# Motor_driver.net
KiCad netlist of a schematic drawn in Altium Designer
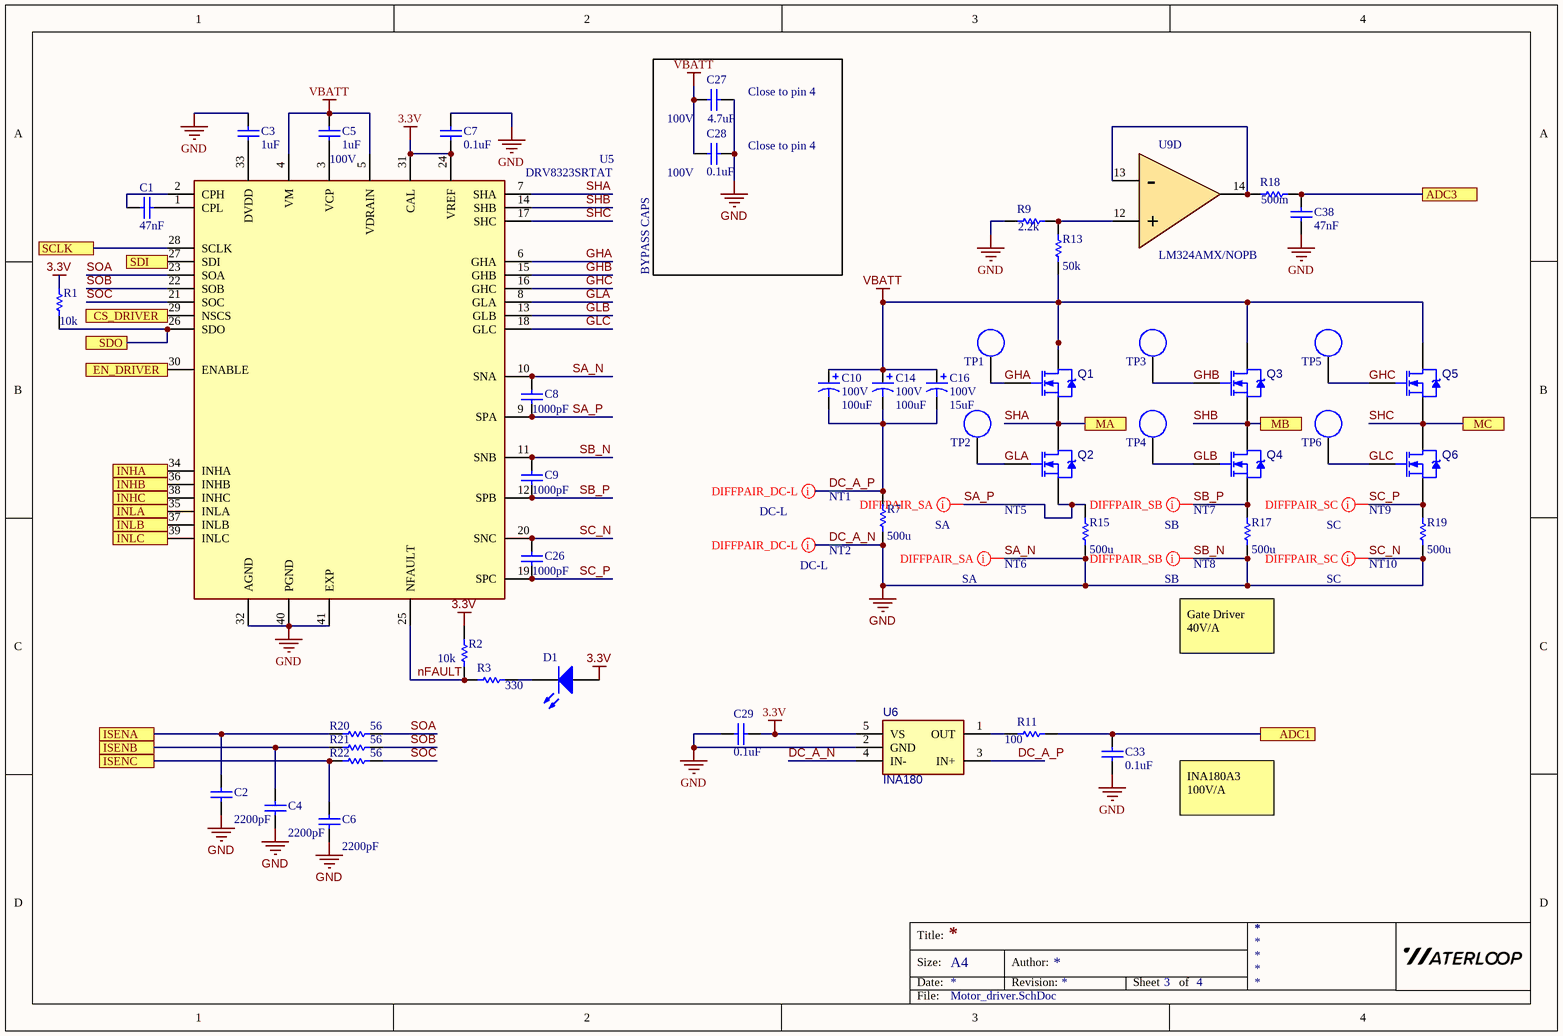
[diagram p0: Motor_driver.SchDoc]

(export (version "E")
  (design (tool "Eeschema 10.0.6"))
  (components
    (comp (ref "C1")
      (value "47nF")
      (footprint "0805 - Capacitor")
      (description "CL21B104KCFNNNE, MULTILAYER CERAMIC CAPACITORS MLCC - SMD/SMT 100NF 100V 0805 ROHS")
      (fields (field (name "Comment") "100V"))
      (libsource (lib "General") (part "Capacitor - Nonpolarized"))
    )
    (comp (ref "C2")
      (value "2200pF")
      (footprint "0805 - Capacitor")
      (description "TDK C2012X7S2A105KT000N, 1UF ±10% 100V X7S 0805 MULTILAYER CERAMIC CAPACITORS MLCC - SMD/SMT ROHS")
      (fields (field (name "Comment") "10V"))
      (libsource (lib "General") (part "Capacitor - Nonpolarized"))
    )
    (comp (ref "C3")
      (value "1uF")
      (footprint "0805 - Capacitor")
      (description "TDK C2012X7S2A105KT000N, 1UF ±10% 100V X7S 0805 MULTILAYER CERAMIC CAPACITORS MLCC - SMD/SMT ROHS")
      (fields (field (name "Comment") "100V"))
      (libsource (lib "General") (part "Capacitor - Nonpolarized"))
    )
    (comp (ref "C4")
      (value "2200pF")
      (footprint "0805 - Capacitor")
      (description "TDK C2012X7S2A105KT000N, 1UF ±10% 100V X7S 0805 MULTILAYER CERAMIC CAPACITORS MLCC - SMD/SMT ROHS")
      (fields (field (name "Comment") "10V"))
      (libsource (lib "General") (part "Capacitor - Nonpolarized"))
    )
    (comp (ref "C5")
      (value "100V")
      (footprint "0805 - Capacitor")
      (description "TDK C2012X7S2A105KT000N, 1UF ±10% 100V X7S 0805 MULTILAYER CERAMIC CAPACITORS MLCC - SMD/SMT ROHS")
      (fields (field (name "ALTIUM_VALUE") "1uF"))
      (libsource (lib "General") (part "Capacitor - Nonpolarized"))
    )
    (comp (ref "C6")
      (value "2200pF")
      (footprint "0805 - Capacitor")
      (description "TDK C2012X7S2A105KT000N, 1UF ±10% 100V X7S 0805 MULTILAYER CERAMIC CAPACITORS MLCC - SMD/SMT ROHS")
      (fields (field (name "Comment") "10V"))
      (libsource (lib "General") (part "Capacitor - Nonpolarized"))
    )
    (comp (ref "C7")
      (value "0.1uF")
      (footprint "0805 - Capacitor")
      (description "CL21B104KCFNNNE, MULTILAYER CERAMIC CAPACITORS MLCC - SMD/SMT 100NF 100V 0805 ROHS")
      (fields (field (name "Comment") "100V"))
      (libsource (lib "General") (part "Capacitor - Nonpolarized"))
    )
    (comp (ref "C8")
      (value "1000pF")
      (footprint "0805 - Capacitor")
      (description "TDK C2012X7S2A105KT000N, 1UF ±10% 100V X7S 0805 MULTILAYER CERAMIC CAPACITORS MLCC - SMD/SMT ROHS")
      (fields (field (name "Comment") "10V"))
      (libsource (lib "General") (part "Capacitor - Nonpolarized"))
    )
    (comp (ref "C9")
      (value "1000pF")
      (footprint "0805 - Capacitor")
      (description "TDK C2012X7S2A105KT000N, 1UF ±10% 100V X7S 0805 MULTILAYER CERAMIC CAPACITORS MLCC - SMD/SMT ROHS")
      (fields (field (name "Comment") "10V"))
      (libsource (lib "General") (part "Capacitor - Nonpolarized"))
    )
    (comp (ref "C10")
      (value "100V")
      (footprint "Electrolytic Cap")
      (fields (field (name "ALTIUM_VALUE") "100uF") (field (name "PUBLISHER") "Altium Limited"))
      (libsource (lib "Miscellaneous Devices") (part "Cap Pol3"))
    )
    (comp (ref "C14")
      (value "100V")
      (footprint "Electrolytic Cap")
      (fields (field (name "ALTIUM_VALUE") "100uF") (field (name "PUBLISHER") "Altium Limited"))
      (libsource (lib "Miscellaneous Devices") (part "Cap Pol3"))
    )
    (comp (ref "C16")
      (value "100V")
      (footprint "Electrolytic Cap")
      (fields (field (name "ALTIUM_VALUE") "15uF") (field (name "PUBLISHER") "Altium Limited"))
      (libsource (lib "Miscellaneous Devices") (part "Cap Pol3"))
    )
    (comp (ref "C26")
      (value "1000pF")
      (footprint "0805 - Capacitor")
      (description "TDK C2012X7S2A105KT000N, 1UF ±10% 100V X7S 0805 MULTILAYER CERAMIC CAPACITORS MLCC - SMD/SMT ROHS")
      (fields (field (name "Comment") "10V"))
      (libsource (lib "General") (part "Capacitor - Nonpolarized"))
    )
    (comp (ref "C27")
      (value "100V")
      (footprint "1210 - Capacitor")
      (description "TDK C2012X7S2A105KT000N, 1UF ±10% 100V X7S 0805 MULTILAYER CERAMIC CAPACITORS MLCC - SMD/SMT ROHS")
      (fields (field (name "ALTIUM_VALUE") "4.7uF"))
      (libsource (lib "General") (part "Capacitor - Nonpolarized"))
    )
    (comp (ref "C28")
      (value "100V")
      (footprint "0805 - Capacitor")
      (description "CL21B104KCFNNNE, MULTILAYER CERAMIC CAPACITORS MLCC - SMD/SMT 100NF 100V 0805 ROHS")
      (fields (field (name "ALTIUM_VALUE") "0.1uF"))
      (libsource (lib "General") (part "Capacitor - Nonpolarized"))
    )
    (comp (ref "C29")
      (value "0.1uF")
      (footprint "0805 - Capacitor")
      (description "CL21B104KCFNNNE, MULTILAYER CERAMIC CAPACITORS MLCC - SMD/SMT 100NF 100V 0805 ROHS")
      (fields (field (name "Comment") "100V"))
      (libsource (lib "General") (part "Capacitor - Nonpolarized"))
    )
    (comp (ref "C33")
      (value "0.1uF")
      (footprint "0805 - Capacitor")
      (description "CL21B104KCFNNNE, MULTILAYER CERAMIC CAPACITORS MLCC - SMD/SMT 100NF 100V 0805 ROHS")
      (fields (field (name "Comment") "100V"))
      (libsource (lib "General") (part "Capacitor - Nonpolarized"))
    )
    (comp (ref "C38")
      (value "47nF")
      (footprint "0805 - Capacitor")
      (description "CL21B104KCFNNNE, MULTILAYER CERAMIC CAPACITORS MLCC - SMD/SMT 100NF 100V 0805 ROHS")
      (fields (field (name "Comment") "100V"))
      (libsource (lib "General") (part "Capacitor - Nonpolarized"))
    )
    (comp (ref "D1")
      (value "150080SS75000")
      (footprint "0805_A")
      (description "SMD mono-color Chip LED, WL-SMCW, Super Red")
      (fields (field (name "MANUFACTURER") "Wuerth Elektronik"))
      (libsource (lib "Altium Content Vault") (part "WE-LED_K1A2-2"))
    )
    (comp (ref "NT1") (value "NetTie") (footprint "Net Tie") (libsource (lib "General") (part "Net Tie")))
    (comp (ref "NT2") (value "NetTie") (footprint "Net Tie") (libsource (lib "General") (part "Net Tie")))
    (comp (ref "NT5") (value "NetTie") (footprint "Net Tie") (libsource (lib "General") (part "Net Tie")))
    (comp (ref "NT6") (value "NetTie") (footprint "Net Tie") (libsource (lib "General") (part "Net Tie")))
    (comp (ref "NT7") (value "NetTie") (footprint "Net Tie") (libsource (lib "General") (part "Net Tie")))
    (comp (ref "NT8") (value "NetTie") (footprint "Net Tie") (libsource (lib "General") (part "Net Tie")))
    (comp (ref "NT9") (value "NetTie") (footprint "Net Tie") (libsource (lib "General") (part "Net Tie")))
    (comp (ref "NT10") (value "NetTie") (footprint "Net Tie") (libsource (lib "General") (part "Net Tie")))
    (comp (ref "Q1")
      (value "NMOS-2")
      (footprint "TO254P1651X1067X470-3")
      (description "N-Channel Power MOSFET")
      (fields (field (name "PUBLISHER") "Altium Limited"))
      (libsource (lib "Miscellaneous Devices") (part "NMOS-2"))
    )
    (comp (ref "Q2")
      (value "NMOS-2")
      (footprint "TO254P1651X1067X470-3")
      (description "N-Channel Power MOSFET")
      (fields (field (name "PUBLISHER") "Altium Limited"))
      (libsource (lib "Miscellaneous Devices") (part "NMOS-2"))
    )
    (comp (ref "Q3")
      (value "NMOS-2")
      (footprint "TO254P1651X1067X470-3")
      (description "N-Channel Power MOSFET")
      (fields (field (name "PUBLISHER") "Altium Limited"))
      (libsource (lib "Miscellaneous Devices") (part "NMOS-2"))
    )
    (comp (ref "Q4")
      (value "NMOS-2")
      (footprint "TO254P1651X1067X470-3")
      (description "N-Channel Power MOSFET")
      (fields (field (name "PUBLISHER") "Altium Limited"))
      (libsource (lib "Miscellaneous Devices") (part "NMOS-2"))
    )
    (comp (ref "Q5")
      (value "NMOS-2")
      (footprint "TO254P1651X1067X470-3")
      (description "N-Channel Power MOSFET")
      (fields (field (name "PUBLISHER") "Altium Limited"))
      (libsource (lib "Miscellaneous Devices") (part "NMOS-2"))
    )
    (comp (ref "Q6")
      (value "NMOS-2")
      (footprint "TO254P1651X1067X470-3")
      (description "N-Channel Power MOSFET")
      (fields (field (name "PUBLISHER") "Altium Limited"))
      (libsource (lib "Miscellaneous Devices") (part "NMOS-2"))
    )
    (comp (ref "R1")
      (value "10k")
      (footprint "0603 - Resistor")
      (description "Resistor")
      (libsource (lib "General") (part "Resistor"))
    )
    (comp (ref "R2")
      (value "10k")
      (footprint "0603 - Resistor")
      (description "Resistor")
      (libsource (lib "General") (part "Resistor"))
    )
    (comp (ref "R3")
      (value "330")
      (footprint "0603 - Resistor")
      (description "Resistor")
      (libsource (lib "General") (part "Resistor"))
    )
    (comp (ref "R7")
      (value "500u")
      (footprint "RESC6430X66N")
      (description "Resistor")
      (libsource (lib "General") (part "Resistor"))
    )
    (comp (ref "R9")
      (value "2.2k")
      (footprint "0603 - Resistor")
      (description "Resistor")
      (libsource (lib "General") (part "Resistor"))
    )
    (comp (ref "R11")
      (value "100")
      (footprint "0603 - Resistor")
      (description "Resistor")
      (libsource (lib "General") (part "Resistor"))
    )
    (comp (ref "R13")
      (value "50k")
      (footprint "0603 - Resistor")
      (description "Resistor")
      (libsource (lib "General") (part "Resistor"))
    )
    (comp (ref "R15")
      (value "500u")
      (footprint "RESC6430X66N")
      (description "Resistor")
      (libsource (lib "General") (part "Resistor"))
    )
    (comp (ref "R17")
      (value "500u")
      (footprint "RESC6430X66N")
      (description "Resistor")
      (libsource (lib "General") (part "Resistor"))
    )
    (comp (ref "R18")
      (value "500m")
      (footprint "0603 - Resistor")
      (description "Resistor")
      (libsource (lib "General") (part "Resistor"))
    )
    (comp (ref "R19")
      (value "500u")
      (footprint "RESC6430X66N")
      (description "Resistor")
      (libsource (lib "General") (part "Resistor"))
    )
    (comp (ref "R20")
      (value "56")
      (footprint "0603 - Resistor")
      (description "Resistor")
      (libsource (lib "General") (part "Resistor"))
    )
    (comp (ref "R21")
      (value "56")
      (footprint "0603 - Resistor")
      (description "Resistor")
      (libsource (lib "General") (part "Resistor"))
    )
    (comp (ref "R22")
      (value "56")
      (footprint "0603 - Resistor")
      (description "Resistor")
      (libsource (lib "General") (part "Resistor"))
    )
    (comp (ref "TP1")
      (value "Test Point")
      (footprint "Test Point")
      (libsource (lib "General") (part "Test Point"))
    )
    (comp (ref "TP2")
      (value "Test Point")
      (footprint "Test Point")
      (libsource (lib "General") (part "Test Point"))
    )
    (comp (ref "TP3")
      (value "Test Point")
      (footprint "Test Point")
      (libsource (lib "General") (part "Test Point"))
    )
    (comp (ref "TP4")
      (value "Test Point")
      (footprint "Test Point")
      (libsource (lib "General") (part "Test Point"))
    )
    (comp (ref "TP5")
      (value "Test Point")
      (footprint "Test Point")
      (libsource (lib "General") (part "Test Point"))
    )
    (comp (ref "TP6")
      (value "Test Point")
      (footprint "Test Point")
      (libsource (lib "General") (part "Test Point"))
    )
    (comp (ref "U5")
      (value "DRV8323SRTAT")
      (footprint "DRV8323SRTAT")
      (description "Multiphase Motor Driver Power MOSFET SPI 40-WQFN _6x6_")
      (fields (field (name "MF") "Texas Instruments"))
      (libsource (lib "MC") (part "DRV8323SRTAT"))
    )
    (comp (ref "U6")
      (value "INA180")
      (footprint "INA180")
      (description "0V to 26V Current Sense Amplifier")
      (fields
        (field (name "MANUFACTURER") "Texas Instruments")
        (field (name "MANUFACTURER PART NUMBER") "INA180A2IDBVR")
      )
      (libsource (lib "GeneralComponents") (part "INA180"))
    )
    (comp (ref "U9")
      (value "LM324AMX/NOPB")
      (footprint "GeneralComponents:LM324AMX/NOPB")
      (description "Gen Purp 4Ch Opamp")
      (fields (field (name "MANUFACTURER") "TI"))
      (libsource (lib "GeneralComponents") (part "LM324AMX/NOPB"))
    )
  )
  (nets
    (net (code "1") (name "/ADC1") (class "Default")
      (node (ref "C33") (pin "1") (pinfunction "1_1") (pintype "passive"))
      (node (ref "R11") (pin "2") (pinfunction "2_2") (pintype "passive"))
    )
    (net (code "2") (name "/ADC3") (class "Default")
      (node (ref "C38") (pin "2") (pinfunction "2_2") (pintype "passive"))
      (node (ref "R18") (pin "2") (pinfunction "2_2") (pintype "passive"))
    )
    (net (code "3") (name "/CS_DRIVER") (class "Default")
      (node (ref "U5") (pin "29") (pinfunction "NSCS_29") (pintype "passive"))
    )
    (net (code "4") (name "/DC_A_N") (class "Default")
      (node (ref "NT2") (pin "1") (pinfunction "1_1") (pintype "passive"))
      (node (ref "U6") (pin "4") (pinfunction "IN-_4") (pintype "passive"))
    )
    (net (code "5") (name "/DC_A_P") (class "Default")
      (node (ref "NT1") (pin "1") (pinfunction "1_1") (pintype "passive"))
      (node (ref "U6") (pin "3") (pinfunction "IN+_3") (pintype "passive"))
    )
    (net (code "6") (name "/EN_DRIVER") (class "Default")
      (node (ref "U5") (pin "30") (pinfunction "ENABLE_30") (pintype "passive"))
    )
    (net (code "7") (name "/GHA") (class "Default")
      (node (ref "Q1") (pin "1") (pinfunction "G_1") (pintype "passive"))
      (node (ref "TP1") (pin "0") (pinfunction "0_0") (pintype "passive"))
      (node (ref "U5") (pin "6") (pinfunction "GHA_6") (pintype "passive"))
    )
    (net (code "8") (name "/GHB") (class "Default")
      (node (ref "Q3") (pin "1") (pinfunction "G_1") (pintype "passive"))
      (node (ref "TP3") (pin "0") (pinfunction "0_0") (pintype "passive"))
      (node (ref "U5") (pin "15") (pinfunction "GHB_15") (pintype "passive"))
    )
    (net (code "9") (name "/GHC") (class "Default")
      (node (ref "Q5") (pin "1") (pinfunction "G_1") (pintype "passive"))
      (node (ref "TP5") (pin "0") (pinfunction "0_0") (pintype "passive"))
      (node (ref "U5") (pin "16") (pinfunction "GHC_16") (pintype "passive"))
    )
    (net (code "10") (name "/GLA") (class "Default")
      (node (ref "Q2") (pin "1") (pinfunction "G_1") (pintype "passive"))
      (node (ref "TP2") (pin "0") (pinfunction "0_0") (pintype "passive"))
      (node (ref "U5") (pin "8") (pinfunction "GLA_8") (pintype "passive"))
    )
    (net (code "11") (name "/GLB") (class "Default")
      (node (ref "Q4") (pin "1") (pinfunction "G_1") (pintype "passive"))
      (node (ref "TP4") (pin "0") (pinfunction "0_0") (pintype "passive"))
      (node (ref "U5") (pin "13") (pinfunction "GLB_13") (pintype "passive"))
    )
    (net (code "12") (name "/GLC") (class "Default")
      (node (ref "Q6") (pin "1") (pinfunction "G_1") (pintype "passive"))
      (node (ref "TP6") (pin "0") (pinfunction "0_0") (pintype "passive"))
      (node (ref "U5") (pin "18") (pinfunction "GLC_18") (pintype "passive"))
    )
    (net (code "13") (name "/INHA") (class "Default")
      (node (ref "U5") (pin "34") (pinfunction "INHA_34") (pintype "passive"))
    )
    (net (code "14") (name "/INHB") (class "Default")
      (node (ref "U5") (pin "36") (pinfunction "INHB_36") (pintype "passive"))
    )
    (net (code "15") (name "/INHC") (class "Default")
      (node (ref "U5") (pin "38") (pinfunction "INHC_38") (pintype "passive"))
    )
    (net (code "16") (name "/INLA") (class "Default")
      (node (ref "U5") (pin "35") (pinfunction "INLA_35") (pintype "passive"))
    )
    (net (code "17") (name "/INLB") (class "Default")
      (node (ref "U5") (pin "37") (pinfunction "INLB_37") (pintype "passive"))
    )
    (net (code "18") (name "/INLC") (class "Default")
      (node (ref "U5") (pin "39") (pinfunction "INLC_39") (pintype "passive"))
    )
    (net (code "19") (name "/ISENA") (class "Default")
      (node (ref "C2") (pin "1") (pinfunction "1_1") (pintype "passive"))
      (node (ref "R20") (pin "2") (pinfunction "2_2") (pintype "passive"))
    )
    (net (code "20") (name "/ISENB") (class "Default")
      (node (ref "C4") (pin "1") (pinfunction "1_1") (pintype "passive"))
      (node (ref "R21") (pin "2") (pinfunction "2_2") (pintype "passive"))
    )
    (net (code "21") (name "/ISENC") (class "Default")
      (node (ref "C6") (pin "1") (pinfunction "1_1") (pintype "passive"))
      (node (ref "R22") (pin "2") (pinfunction "2_2") (pintype "passive"))
    )
    (net (code "22") (name "/SA_N") (class "Default")
      (node (ref "C8") (pin "1") (pinfunction "1_1") (pintype "passive"))
      (node (ref "NT6") (pin "1") (pinfunction "1_1") (pintype "passive"))
      (node (ref "U5") (pin "10") (pinfunction "SNA_10") (pintype "passive"))
    )
    (net (code "23") (name "/SA_P") (class "Default")
      (node (ref "C8") (pin "2") (pinfunction "2_2") (pintype "passive"))
      (node (ref "NT5") (pin "1") (pinfunction "1_1") (pintype "passive"))
      (node (ref "U5") (pin "9") (pinfunction "SPA_9") (pintype "passive"))
    )
    (net (code "24") (name "/SB_N") (class "Default")
      (node (ref "C9") (pin "1") (pinfunction "1_1") (pintype "passive"))
      (node (ref "NT8") (pin "1") (pinfunction "1_1") (pintype "passive"))
      (node (ref "U5") (pin "11") (pinfunction "SNB_11") (pintype "passive"))
    )
    (net (code "25") (name "/SB_P") (class "Default")
      (node (ref "C9") (pin "2") (pinfunction "2_2") (pintype "passive"))
      (node (ref "NT7") (pin "1") (pinfunction "1_1") (pintype "passive"))
      (node (ref "U5") (pin "12") (pinfunction "SPB_12") (pintype "passive"))
    )
    (net (code "26") (name "/SCLK") (class "Default")
      (node (ref "U5") (pin "28") (pinfunction "SCLK_28") (pintype "passive"))
    )
    (net (code "27") (name "/SC_N") (class "Default")
      (node (ref "C26") (pin "1") (pinfunction "1_1") (pintype "passive"))
      (node (ref "NT10") (pin "1") (pinfunction "1_1") (pintype "passive"))
      (node (ref "U5") (pin "20") (pinfunction "SNC_20") (pintype "passive"))
    )
    (net (code "28") (name "/SC_P") (class "Default")
      (node (ref "C26") (pin "2") (pinfunction "2_2") (pintype "passive"))
      (node (ref "NT9") (pin "1") (pinfunction "1_1") (pintype "passive"))
      (node (ref "U5") (pin "19") (pinfunction "SPC_19") (pintype "passive"))
    )
    (net (code "29") (name "/SDI") (class "Default")
      (node (ref "U5") (pin "27") (pinfunction "SDI_27") (pintype "passive"))
    )
    (net (code "30") (name "/SDO") (class "Default")
      (node (ref "R1") (pin "2") (pinfunction "2_2") (pintype "passive"))
      (node (ref "U5") (pin "26") (pinfunction "SDO_26") (pintype "passive"))
    )
    (net (code "31") (name "/SHA") (class "Default")
      (node (ref "Q1") (pin "3") (pinfunction "S_3") (pintype "passive"))
      (node (ref "Q2") (pin "2") (pinfunction "D_2") (pintype "passive"))
      (node (ref "U5") (pin "7") (pinfunction "SHA_7") (pintype "passive"))
    )
    (net (code "32") (name "/SHB") (class "Default")
      (node (ref "Q3") (pin "3") (pinfunction "S_3") (pintype "passive"))
      (node (ref "Q4") (pin "2") (pinfunction "D_2") (pintype "passive"))
      (node (ref "U5") (pin "14") (pinfunction "SHB_14") (pintype "passive"))
    )
    (net (code "33") (name "/SHC") (class "Default")
      (node (ref "Q5") (pin "3") (pinfunction "S_3") (pintype "passive"))
      (node (ref "Q6") (pin "2") (pinfunction "D_2") (pintype "passive"))
      (node (ref "U5") (pin "17") (pinfunction "SHC_17") (pintype "passive"))
    )
    (net (code "34") (name "/SOA") (class "Default")
      (node (ref "R20") (pin "1") (pinfunction "1_1") (pintype "passive"))
      (node (ref "U5") (pin "23") (pinfunction "SOA_23") (pintype "passive"))
    )
    (net (code "35") (name "/SOB") (class "Default")
      (node (ref "R21") (pin "1") (pinfunction "1_1") (pintype "passive"))
      (node (ref "U5") (pin "22") (pinfunction "SOB_22") (pintype "passive"))
    )
    (net (code "36") (name "/SOC") (class "Default")
      (node (ref "R22") (pin "1") (pinfunction "1_1") (pintype "passive"))
      (node (ref "U5") (pin "21") (pinfunction "SOC_21") (pintype "passive"))
    )
    (net (code "37") (name "/nFAULT") (class "Default")
      (node (ref "R2") (pin "2") (pinfunction "2_2") (pintype "passive"))
      (node (ref "R3") (pin "2") (pinfunction "2_2") (pintype "passive"))
      (node (ref "U5") (pin "25") (pinfunction "NFAULT_25") (pintype "passive"))
    )
    (net (code "38") (name "3.3V") (class "Default")
      (node (ref "C29") (pin "1") (pinfunction "1_1") (pintype "passive"))
      (node (ref "C7") (pin "1") (pinfunction "1_1") (pintype "passive"))
      (node (ref "D1") (pin "2") (pinfunction "A_2") (pintype "passive"))
      (node (ref "R1") (pin "1") (pinfunction "1_1") (pintype "passive"))
      (node (ref "R2") (pin "1") (pinfunction "1_1") (pintype "passive"))
      (node (ref "U5") (pin "24") (pinfunction "VREF_24") (pintype "passive"))
      (node (ref "U5") (pin "31") (pinfunction "CAL_31") (pintype "passive"))
      (node (ref "U6") (pin "5") (pinfunction "VS_5") (pintype "passive"))
    )
    (net (code "39") (name "GND") (class "Default")
      (node (ref "C2") (pin "2") (pinfunction "2_2") (pintype "passive"))
      (node (ref "C27") (pin "1") (pinfunction "1_1") (pintype "passive"))
      (node (ref "C28") (pin "1") (pinfunction "1_1") (pintype "passive"))
      (node (ref "C29") (pin "2") (pinfunction "2_2") (pintype "passive"))
      (node (ref "C3") (pin "2") (pinfunction "2_2") (pintype "passive"))
      (node (ref "C33") (pin "2") (pinfunction "2_2") (pintype "passive"))
      (node (ref "C38") (pin "1") (pinfunction "1_1") (pintype "passive"))
      (node (ref "C4") (pin "2") (pinfunction "2_2") (pintype "passive"))
      (node (ref "C6") (pin "2") (pinfunction "2_2") (pintype "passive"))
      (node (ref "C7") (pin "2") (pinfunction "2_2") (pintype "passive"))
      (node (ref "NT10") (pin "2") (pinfunction "2_2") (pintype "passive"))
      (node (ref "NT2") (pin "2") (pinfunction "2_2") (pintype "passive"))
      (node (ref "NT6") (pin "2") (pinfunction "2_2") (pintype "passive"))
      (node (ref "NT8") (pin "2") (pinfunction "2_2") (pintype "passive"))
      (node (ref "R15") (pin "1") (pinfunction "1_1") (pintype "passive"))
      (node (ref "R17") (pin "1") (pinfunction "1_1") (pintype "passive"))
      (node (ref "R19") (pin "1") (pinfunction "1_1") (pintype "passive"))
      (node (ref "R7") (pin "1") (pinfunction "1_1") (pintype "passive"))
      (node (ref "R9") (pin "1") (pinfunction "1_1") (pintype "passive"))
      (node (ref "U5") (pin "32") (pinfunction "AGND_32") (pintype "passive"))
      (node (ref "U5") (pin "40") (pinfunction "PGND_40") (pintype "passive"))
      (node (ref "U5") (pin "41") (pinfunction "EXP_41") (pintype "passive"))
      (node (ref "U6") (pin "2") (pinfunction "GND_2") (pintype "passive"))
    )
    (net (code "40") (name "Net-(C10-Pad2)") (class "Default")
      (node (ref "C10") (pin "2") (pinfunction "2_2") (pintype "passive"))
      (node (ref "C14") (pin "2") (pinfunction "2_2") (pintype "passive"))
      (node (ref "C16") (pin "2") (pinfunction "2_2") (pintype "passive"))
      (node (ref "NT1") (pin "2") (pinfunction "2_2") (pintype "passive"))
      (node (ref "R7") (pin "2") (pinfunction "2_2") (pintype "passive"))
    )
    (net (code "41") (name "Net-(D1-K)") (class "Default")
      (node (ref "D1") (pin "1") (pinfunction "K_1") (pintype "passive"))
      (node (ref "R3") (pin "1") (pinfunction "1_1") (pintype "passive"))
    )
    (net (code "42") (name "Net-(Q2-S)") (class "Default")
      (node (ref "NT5") (pin "2") (pinfunction "2_2") (pintype "passive"))
      (node (ref "Q2") (pin "3") (pinfunction "S_3") (pintype "passive"))
      (node (ref "R15") (pin "2") (pinfunction "2_2") (pintype "passive"))
    )
    (net (code "43") (name "Net-(Q4-S)") (class "Default")
      (node (ref "NT7") (pin "2") (pinfunction "2_2") (pintype "passive"))
      (node (ref "Q4") (pin "3") (pinfunction "S_3") (pintype "passive"))
      (node (ref "R17") (pin "2") (pinfunction "2_2") (pintype "passive"))
    )
    (net (code "44") (name "Net-(Q6-S)") (class "Default")
      (node (ref "NT9") (pin "2") (pinfunction "2_2") (pintype "passive"))
      (node (ref "Q6") (pin "3") (pinfunction "S_3") (pintype "passive"))
      (node (ref "R19") (pin "2") (pinfunction "2_2") (pintype "passive"))
    )
    (net (code "45") (name "Net-(U5-CPH)") (class "Default")
      (node (ref "C1") (pin "2") (pinfunction "2_2") (pintype "passive"))
      (node (ref "U5") (pin "2") (pinfunction "CPH_2") (pintype "passive"))
    )
    (net (code "46") (name "Net-(U5-CPL)") (class "Default")
      (node (ref "C1") (pin "1") (pinfunction "1_1") (pintype "passive"))
      (node (ref "U5") (pin "1") (pinfunction "CPL_1") (pintype "passive"))
    )
    (net (code "47") (name "Net-(U5-DVDD)") (class "Default")
      (node (ref "C3") (pin "1") (pinfunction "1_1") (pintype "passive"))
      (node (ref "U5") (pin "33") (pinfunction "DVDD_33") (pintype "passive"))
    )
    (net (code "48") (name "Net-(U5-VCP)") (class "Default")
      (node (ref "C5") (pin "1") (pinfunction "1_1") (pintype "passive"))
      (node (ref "U5") (pin "3") (pinfunction "VCP_3") (pintype "passive"))
    )
    (net (code "49") (name "Net-(U6-OUT)") (class "Default")
      (node (ref "R11") (pin "1") (pinfunction "1_1") (pintype "passive"))
      (node (ref "U6") (pin "1") (pinfunction "OUT_1") (pintype "passive"))
    )
    (net (code "50") (name "Net-(U9D-+)") (class "Default")
      (node (ref "R13") (pin "1") (pinfunction "1_1") (pintype "passive"))
      (node (ref "R9") (pin "2") (pinfunction "2_2") (pintype "passive"))
      (node (ref "U9") (pin "12") (pinfunction "+_12") (pintype "passive"))
    )
    (net (code "51") (name "Net-(U9D--)") (class "Default")
      (node (ref "R18") (pin "1") (pinfunction "1_1") (pintype "passive"))
      (node (ref "U9") (pin "13") (pinfunction "-_13") (pintype "passive"))
      (node (ref "U9") (pin "14") (pinfunction "14_14") (pintype "passive"))
    )
    (net (code "52") (name "VBATT") (class "Default")
      (node (ref "C10") (pin "1") (pinfunction "1_1") (pintype "passive"))
      (node (ref "C14") (pin "1") (pinfunction "1_1") (pintype "passive"))
      (node (ref "C16") (pin "1") (pinfunction "1_1") (pintype "passive"))
      (node (ref "C27") (pin "2") (pinfunction "2_2") (pintype "passive"))
      (node (ref "C28") (pin "2") (pinfunction "2_2") (pintype "passive"))
      (node (ref "C5") (pin "2") (pinfunction "2_2") (pintype "passive"))
      (node (ref "Q1") (pin "2") (pinfunction "D_2") (pintype "passive"))
      (node (ref "Q3") (pin "2") (pinfunction "D_2") (pintype "passive"))
      (node (ref "Q5") (pin "2") (pinfunction "D_2") (pintype "passive"))
      (node (ref "R13") (pin "2") (pinfunction "2_2") (pintype "passive"))
      (node (ref "U5") (pin "4") (pinfunction "VM_4") (pintype "passive"))
      (node (ref "U5") (pin "5") (pinfunction "VDRAIN_5") (pintype "passive"))
    )
  )
)
